# battery_09_26_2017.net
KiCad netlist of a schematic drawn in EAGLE
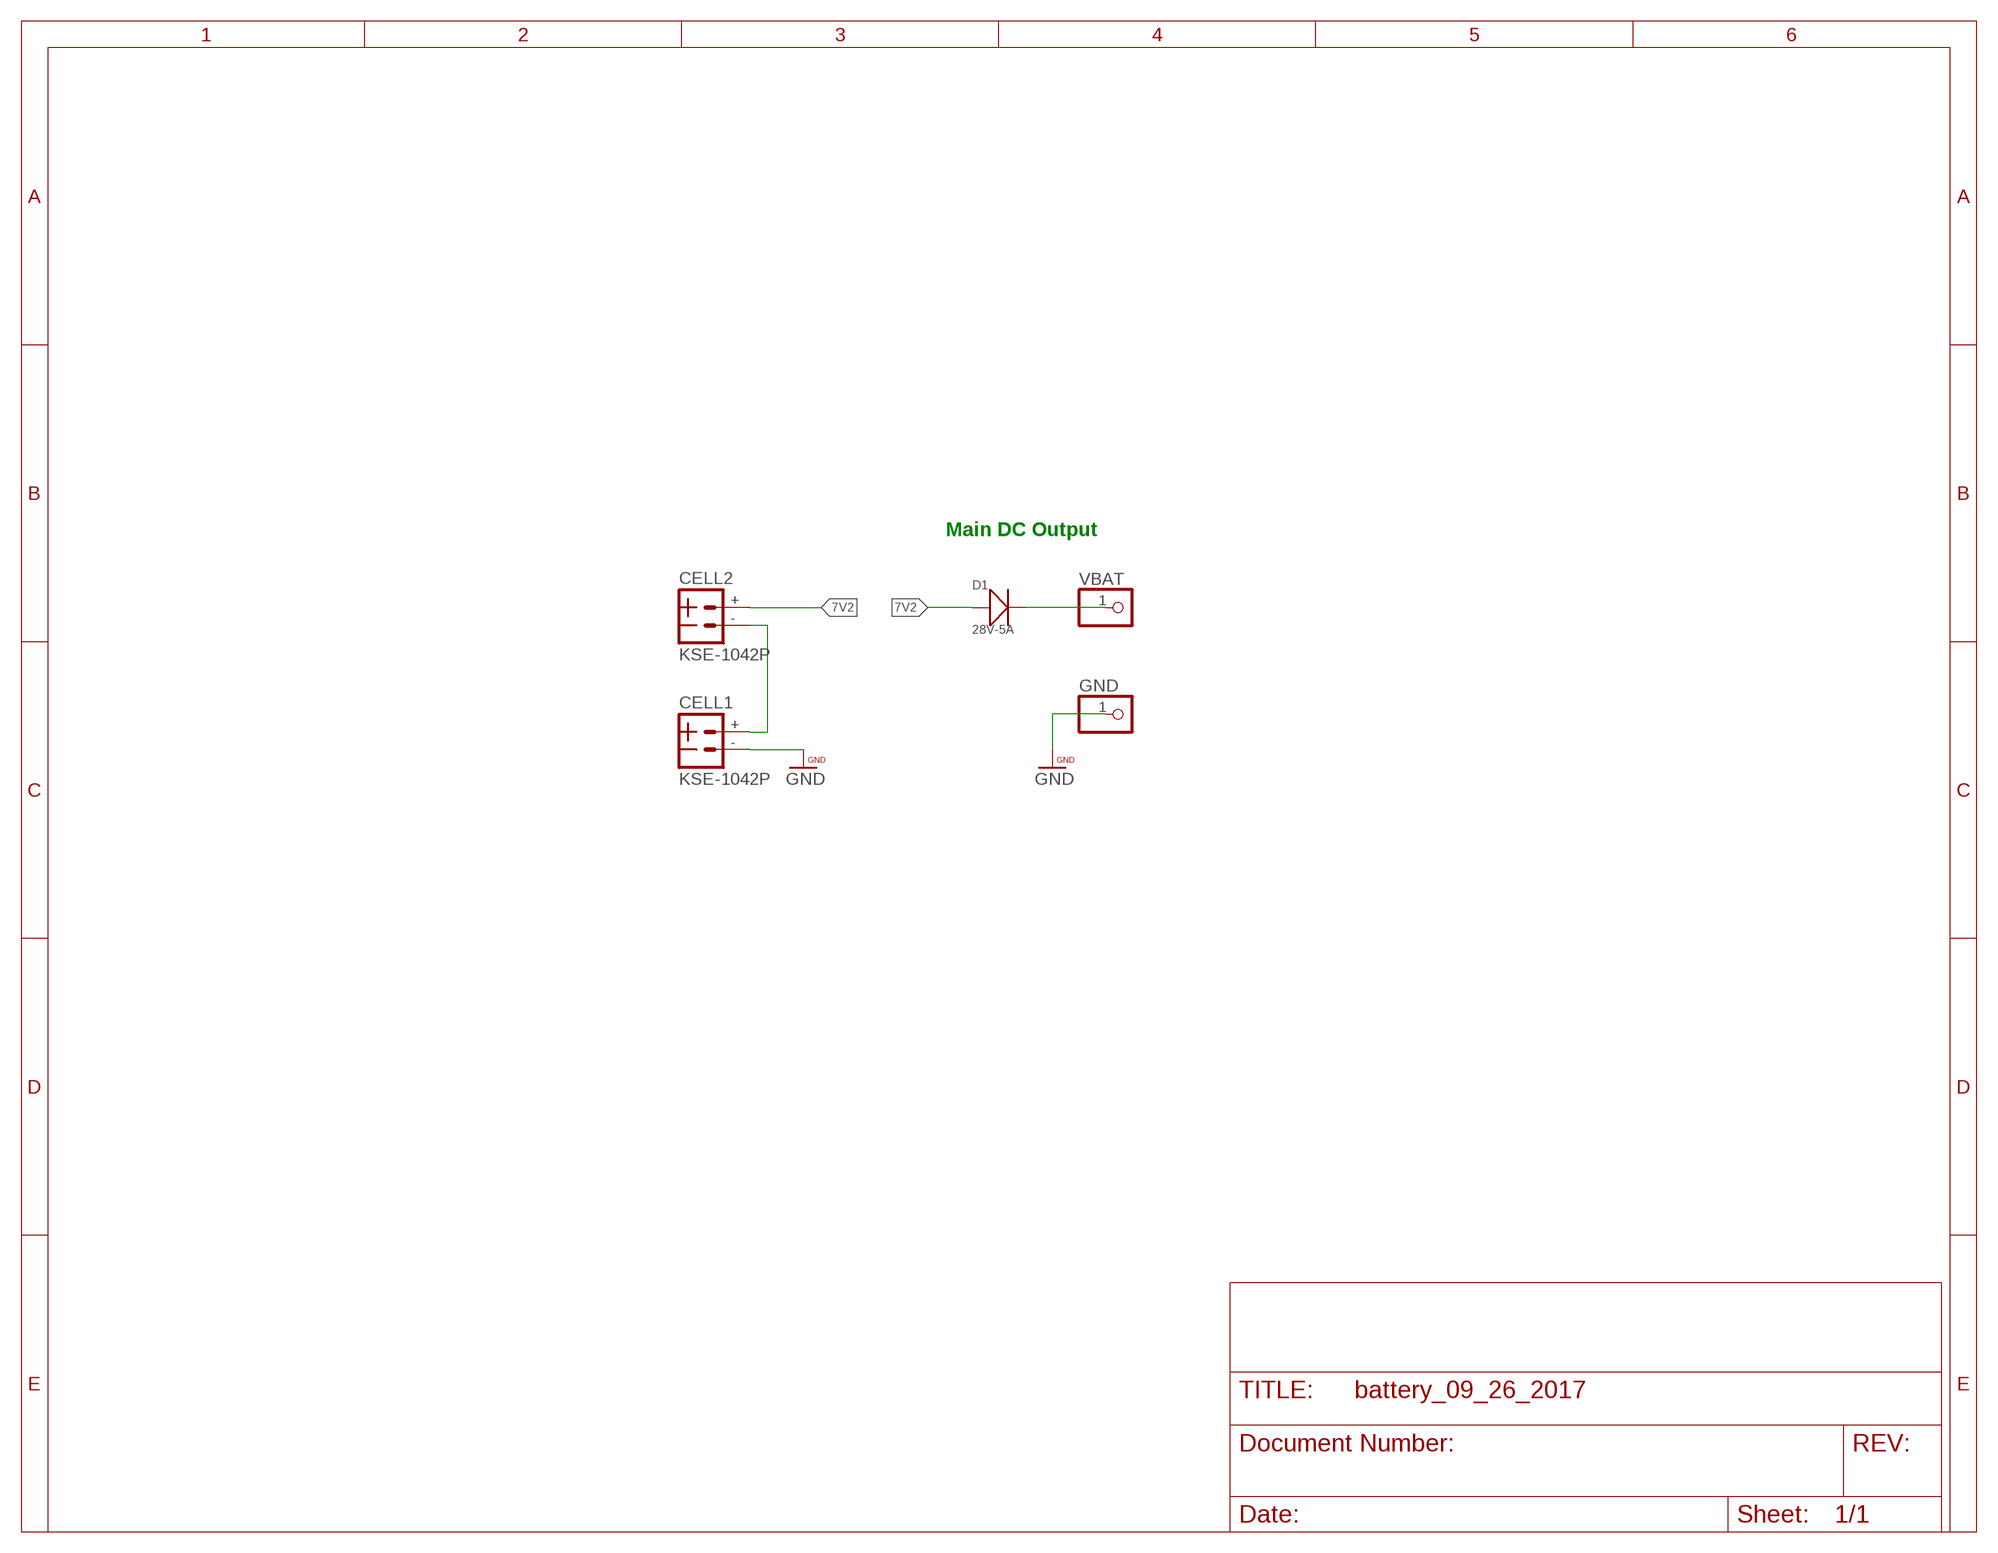
[diagram p0: schematic, sheet 1]

(export (version "E")
  (design (tool "Eeschema 10.0.6"))
  (components
    (comp (ref "CELL1")
      (value "KSE-1042P")
      (footprint "eagle-import:KSE-1042P")
      (libsource (lib "eagle-import") (part "KSE-1042P"))
    )
    (comp (ref "CELL2")
      (value "KSE-1042P")
      (footprint "eagle-import:KSE-1042P")
      (libsource (lib "eagle-import") (part "KSE-1042P"))
    )
    (comp (ref "D1")
      (value "28V-5A")
      (footprint "eagle-import:DO-214AA")
      (fields (field (name "MPN") "SS54B"))
      (libsource (lib "eagle-import") (part "SMD-DIODE-SCHOTTKY-28V-5A(DO-214AA)"))
    )
    (comp (ref "GND")
      (value "WPAD-1-PTH")
      (footprint "eagle-import:WPAD-1-PTH-2.54")
      (libsource (lib "eagle-import") (part "WPAD-1-PTH"))
    )
    (comp (ref "VBAT")
      (value "WPAD-1-PTH")
      (footprint "eagle-import:WPAD-1-PTH-2.54")
      (libsource (lib "eagle-import") (part "WPAD-1-PTH"))
    )
  )
  (nets
    (net (code "1") (name "7V2") (class "Default")
      (node (ref "CELL2") (pin "+") (pinfunction "+_+") (pintype "passive"))
      (node (ref "D1") (pin "+") (pinfunction "+_+") (pintype "passive"))
    )
    (net (code "2") (name "GND") (class "Default")
      (node (ref "CELL1") (pin "-") (pinfunction "-_-") (pintype "passive"))
      (node (ref "GND") (pin "1") (pinfunction "1_1") (pintype "passive"))
    )
    (net (code "3") (name "Net-(CELL1-Pad+)") (class "Default")
      (node (ref "CELL1") (pin "+") (pinfunction "+_+") (pintype "passive"))
      (node (ref "CELL2") (pin "-") (pinfunction "-_-") (pintype "passive"))
    )
    (net (code "4") (name "Net-(D1-Pad-)") (class "Default")
      (node (ref "D1") (pin "-") (pinfunction "-_-") (pintype "passive"))
      (node (ref "VBAT") (pin "1") (pinfunction "1_1") (pintype "passive"))
    )
  )
)
